# Control.net
KiCad netlist of a schematic drawn in EAGLE
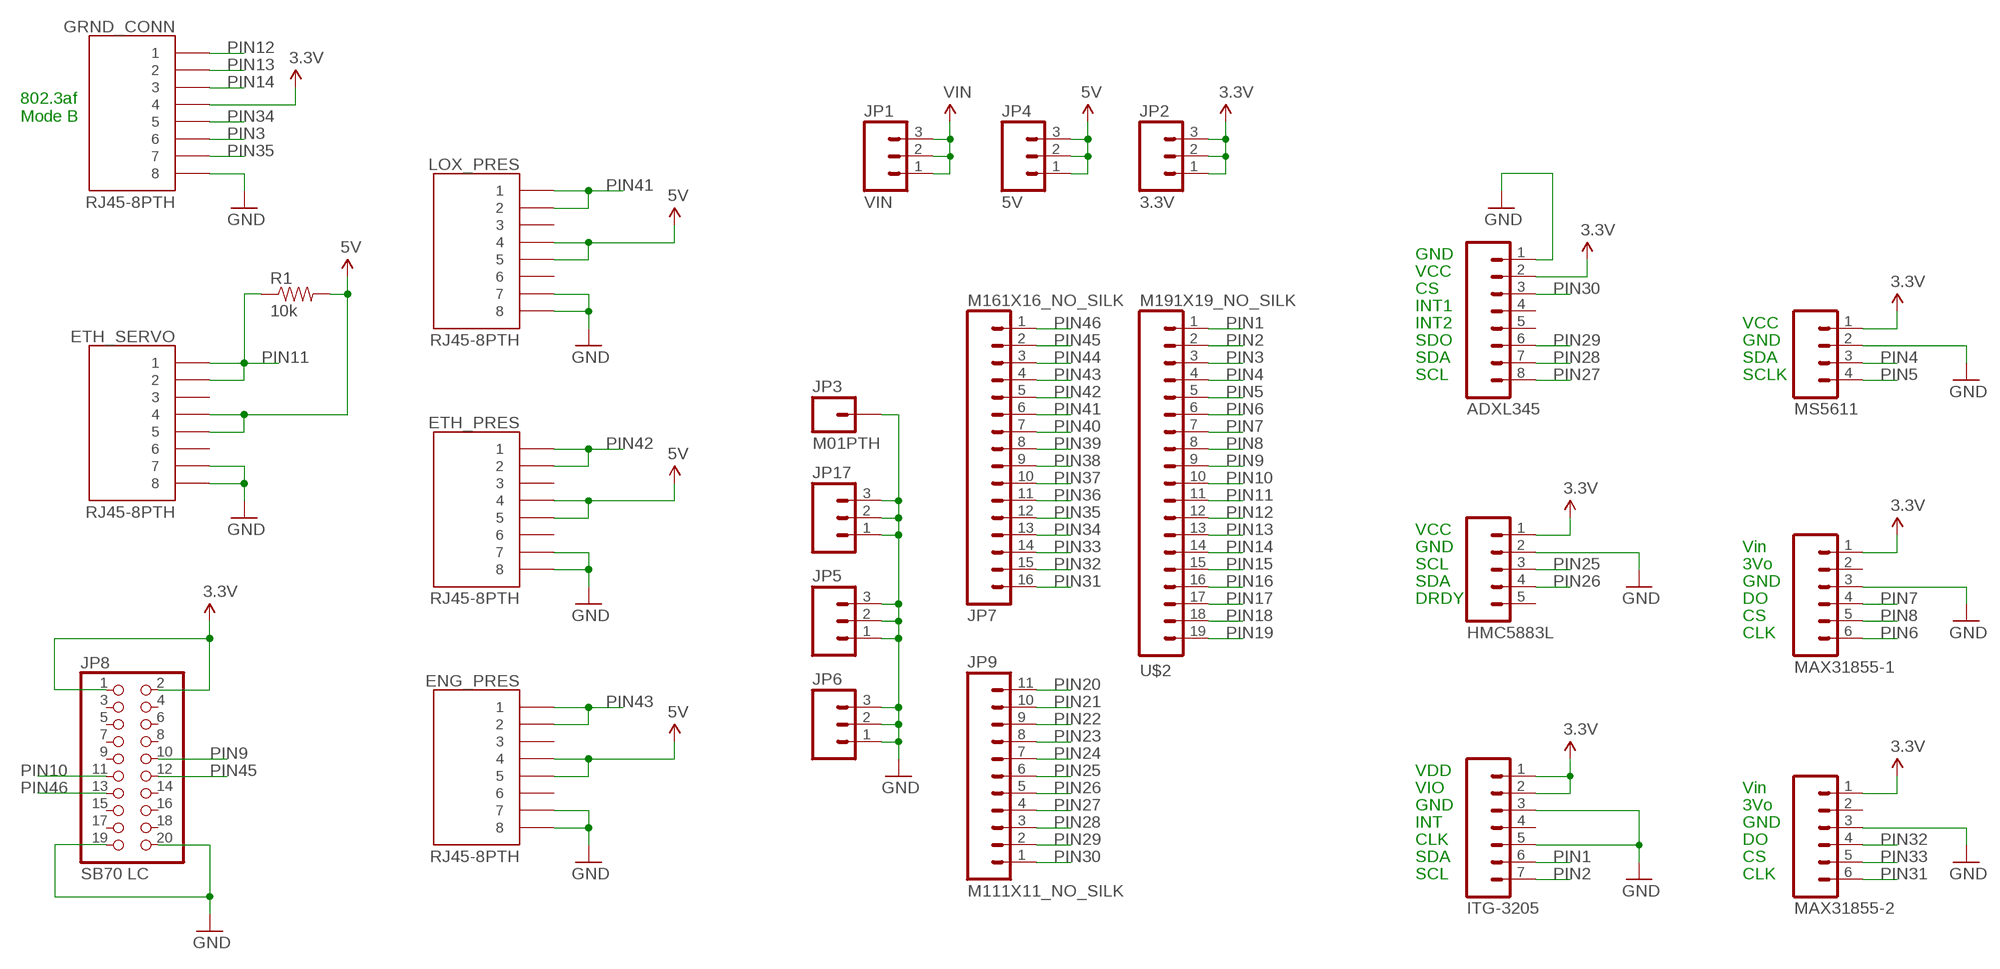
[diagram p0: schematic, sheet 1]

(export (version "E")
  (design (tool "Eeschema 10.0.6"))
  (components
    (comp (ref "ADXL345")
      (value "M081X08")
      (footprint "eagle-import:1X08")
      (libsource (lib "eagle-import") (part "M081X08"))
    )
    (comp (ref "ENG_PRES")
      (value "RJ45-8PTH")
      (footprint "eagle-import:RJ45-8")
      (libsource (lib "eagle-import") (part "RJ45-8PTH"))
    )
    (comp (ref "ETH_PRES")
      (value "RJ45-8PTH")
      (footprint "eagle-import:RJ45-8")
      (libsource (lib "eagle-import") (part "RJ45-8PTH"))
    )
    (comp (ref "ETH_SERVO")
      (value "RJ45-8PTH")
      (footprint "eagle-import:RJ45-8")
      (libsource (lib "eagle-import") (part "RJ45-8PTH"))
    )
    (comp (ref "GRND_CONN")
      (value "RJ45-8PTH")
      (footprint "eagle-import:RJ45-8")
      (libsource (lib "eagle-import") (part "RJ45-8PTH"))
    )
    (comp (ref "HMC5883L")
      (value "M05PTH")
      (footprint "eagle-import:1X05")
      (libsource (lib "eagle-import") (part "M05PTH"))
    )
    (comp (ref "ITG-3205")
      (value "M07")
      (footprint "eagle-import:1X07")
      (libsource (lib "eagle-import") (part "M07"))
    )
    (comp (ref "JP1")
      (value "VIN")
      (footprint "eagle-import:1X03")
      (libsource (lib "eagle-import") (part "M03PTH"))
    )
    (comp (ref "JP2")
      (value "3.3V")
      (footprint "eagle-import:1X03")
      (libsource (lib "eagle-import") (part "M03PTH"))
    )
    (comp (ref "JP3")
      (value "M01PTH")
      (footprint "eagle-import:1X01")
      (libsource (lib "eagle-import") (part "M01PTH"))
    )
    (comp (ref "JP4")
      (value "5V")
      (footprint "eagle-import:1X03")
      (libsource (lib "eagle-import") (part "M03PTH"))
    )
    (comp (ref "JP5")
      (value "M03PTH")
      (footprint "eagle-import:1X03")
      (libsource (lib "eagle-import") (part "M03PTH"))
    )
    (comp (ref "JP6")
      (value "M03PTH")
      (footprint "eagle-import:1X03")
      (libsource (lib "eagle-import") (part "M03PTH"))
    )
    (comp (ref "JP7")
      (value "M161X16_NO_SILK")
      (footprint "eagle-import:1X16_NO_SILK")
      (libsource (lib "eagle-import") (part "M161X16_NO_SILK"))
    )
    (comp (ref "JP8")
      (value "SB70 LC")
      (footprint "eagle-import:2X10")
      (libsource (lib "eagle-import") (part "PINHD-2X10"))
    )
    (comp (ref "JP9")
      (value "M111X11_NO_SILK")
      (footprint "eagle-import:1X11_NO_SILK")
      (libsource (lib "eagle-import") (part "M111X11_NO_SILK"))
    )
    (comp (ref "JP17")
      (value "M03PTH")
      (footprint "eagle-import:1X03")
      (libsource (lib "eagle-import") (part "M03PTH"))
    )
    (comp (ref "LOX_PRES")
      (value "RJ45-8PTH")
      (footprint "eagle-import:RJ45-8")
      (libsource (lib "eagle-import") (part "RJ45-8PTH"))
    )
    (comp (ref "MAX31855-1")
      (value "M06SIP")
      (footprint "eagle-import:1X06")
      (libsource (lib "eagle-import") (part "M06SIP"))
    )
    (comp (ref "MAX31855-2")
      (value "M06SIP")
      (footprint "eagle-import:1X06")
      (libsource (lib "eagle-import") (part "M06SIP"))
    )
    (comp (ref "MS5611")
      (value "M041X04_NO_SILK")
      (footprint "eagle-import:1X04_NO_SILK")
      (libsource (lib "eagle-import") (part "M041X04_NO_SILK"))
    )
    (comp (ref "R1")
      (value "10k")
      (footprint "eagle-import:AXIAL-0.5")
      (libsource (lib "eagle-import") (part "RESISTORPTH-1/2W"))
    )
    (comp (ref "U$2")
      (value "M191X19_NO_SILK")
      (footprint "eagle-import:1X19_NO_SILK")
      (libsource (lib "eagle-import") (part "M191X19_NO_SILK"))
    )
  )
  (nets
    (net (code "1") (name "/PIN1") (class "Default")
      (node (ref "ITG-3205") (pin "6") (pinfunction "6_6") (pintype "passive"))
      (node (ref "U$2") (pin "1") (pinfunction "1_1") (pintype "passive"))
    )
    (net (code "2") (name "/PIN2") (class "Default")
      (node (ref "ITG-3205") (pin "7") (pinfunction "7_7") (pintype "passive"))
      (node (ref "U$2") (pin "2") (pinfunction "2_2") (pintype "passive"))
    )
    (net (code "3") (name "/PIN3") (class "Default")
      (node (ref "GRND_CONN") (pin "6") (pinfunction "6_6") (pintype "bidirectional"))
      (node (ref "U$2") (pin "3") (pinfunction "3_3") (pintype "passive"))
    )
    (net (code "4") (name "/PIN4") (class "Default")
      (node (ref "MS5611") (pin "3") (pinfunction "3_3") (pintype "passive"))
      (node (ref "U$2") (pin "4") (pinfunction "4_4") (pintype "passive"))
    )
    (net (code "5") (name "/PIN5") (class "Default")
      (node (ref "MS5611") (pin "4") (pinfunction "4_4") (pintype "passive"))
      (node (ref "U$2") (pin "5") (pinfunction "5_5") (pintype "passive"))
    )
    (net (code "6") (name "/PIN6") (class "Default")
      (node (ref "MAX31855-1") (pin "6") (pinfunction "6_6") (pintype "passive"))
      (node (ref "U$2") (pin "6") (pinfunction "6_6") (pintype "passive"))
    )
    (net (code "7") (name "/PIN7") (class "Default")
      (node (ref "MAX31855-1") (pin "4") (pinfunction "4_4") (pintype "passive"))
      (node (ref "U$2") (pin "7") (pinfunction "7_7") (pintype "passive"))
    )
    (net (code "8") (name "/PIN8") (class "Default")
      (node (ref "MAX31855-1") (pin "5") (pinfunction "5_5") (pintype "passive"))
      (node (ref "U$2") (pin "8") (pinfunction "8_8") (pintype "passive"))
    )
    (net (code "9") (name "/PIN9") (class "Default")
      (node (ref "JP8") (pin "10") (pinfunction "10_10") (pintype "passive"))
      (node (ref "U$2") (pin "9") (pinfunction "9_9") (pintype "passive"))
    )
    (net (code "10") (name "/PIN10") (class "Default")
      (node (ref "JP8") (pin "11") (pinfunction "11_11") (pintype "passive"))
      (node (ref "U$2") (pin "10") (pinfunction "10_10") (pintype "passive"))
    )
    (net (code "11") (name "/PIN11") (class "Default")
      (node (ref "ETH_SERVO") (pin "1") (pinfunction "1_1") (pintype "bidirectional"))
      (node (ref "ETH_SERVO") (pin "2") (pinfunction "2_2") (pintype "bidirectional"))
      (node (ref "R1") (pin "P$1") (pinfunction "1_P$1") (pintype "passive"))
      (node (ref "U$2") (pin "11") (pinfunction "11_11") (pintype "passive"))
    )
    (net (code "12") (name "/PIN12") (class "Default")
      (node (ref "GRND_CONN") (pin "1") (pinfunction "1_1") (pintype "bidirectional"))
      (node (ref "U$2") (pin "12") (pinfunction "12_12") (pintype "passive"))
    )
    (net (code "13") (name "/PIN13") (class "Default")
      (node (ref "GRND_CONN") (pin "2") (pinfunction "2_2") (pintype "bidirectional"))
      (node (ref "U$2") (pin "13") (pinfunction "13_13") (pintype "passive"))
    )
    (net (code "14") (name "/PIN14") (class "Default")
      (node (ref "GRND_CONN") (pin "3") (pinfunction "3_3") (pintype "bidirectional"))
      (node (ref "U$2") (pin "14") (pinfunction "14_14") (pintype "passive"))
    )
    (net (code "15") (name "/PIN15") (class "Default")
      (node (ref "U$2") (pin "15") (pinfunction "15_15") (pintype "passive"))
    )
    (net (code "16") (name "/PIN16") (class "Default")
      (node (ref "U$2") (pin "16") (pinfunction "16_16") (pintype "passive"))
    )
    (net (code "17") (name "/PIN17") (class "Default")
      (node (ref "U$2") (pin "17") (pinfunction "17_17") (pintype "passive"))
    )
    (net (code "18") (name "/PIN18") (class "Default")
      (node (ref "U$2") (pin "18") (pinfunction "18_18") (pintype "passive"))
    )
    (net (code "19") (name "/PIN19") (class "Default")
      (node (ref "U$2") (pin "19") (pinfunction "19_19") (pintype "passive"))
    )
    (net (code "20") (name "/PIN20") (class "Default")
      (node (ref "JP9") (pin "11") (pinfunction "11_11") (pintype "passive"))
    )
    (net (code "21") (name "/PIN21") (class "Default")
      (node (ref "JP9") (pin "10") (pinfunction "10_10") (pintype "passive"))
    )
    (net (code "22") (name "/PIN22") (class "Default")
      (node (ref "JP9") (pin "9") (pinfunction "9_9") (pintype "passive"))
    )
    (net (code "23") (name "/PIN23") (class "Default")
      (node (ref "JP9") (pin "8") (pinfunction "8_8") (pintype "passive"))
    )
    (net (code "24") (name "/PIN24") (class "Default")
      (node (ref "JP9") (pin "7") (pinfunction "7_7") (pintype "passive"))
    )
    (net (code "25") (name "/PIN25") (class "Default")
      (node (ref "HMC5883L") (pin "3") (pinfunction "3_3") (pintype "passive"))
      (node (ref "JP9") (pin "6") (pinfunction "6_6") (pintype "passive"))
    )
    (net (code "26") (name "/PIN26") (class "Default")
      (node (ref "HMC5883L") (pin "4") (pinfunction "4_4") (pintype "passive"))
      (node (ref "JP9") (pin "5") (pinfunction "5_5") (pintype "passive"))
    )
    (net (code "27") (name "/PIN27") (class "Default")
      (node (ref "ADXL345") (pin "8") (pinfunction "8_8") (pintype "passive"))
      (node (ref "JP9") (pin "4") (pinfunction "4_4") (pintype "passive"))
    )
    (net (code "28") (name "/PIN28") (class "Default")
      (node (ref "ADXL345") (pin "7") (pinfunction "7_7") (pintype "passive"))
      (node (ref "JP9") (pin "3") (pinfunction "3_3") (pintype "passive"))
    )
    (net (code "29") (name "/PIN29") (class "Default")
      (node (ref "ADXL345") (pin "6") (pinfunction "6_6") (pintype "passive"))
      (node (ref "JP9") (pin "2") (pinfunction "2_2") (pintype "passive"))
    )
    (net (code "30") (name "/PIN30") (class "Default")
      (node (ref "ADXL345") (pin "3") (pinfunction "3_3") (pintype "passive"))
      (node (ref "JP9") (pin "1") (pinfunction "1_1") (pintype "passive"))
    )
    (net (code "31") (name "/PIN31") (class "Default")
      (node (ref "JP7") (pin "16") (pinfunction "16_16") (pintype "passive"))
      (node (ref "MAX31855-2") (pin "6") (pinfunction "6_6") (pintype "passive"))
    )
    (net (code "32") (name "/PIN32") (class "Default")
      (node (ref "JP7") (pin "15") (pinfunction "15_15") (pintype "passive"))
      (node (ref "MAX31855-2") (pin "4") (pinfunction "4_4") (pintype "passive"))
    )
    (net (code "33") (name "/PIN33") (class "Default")
      (node (ref "JP7") (pin "14") (pinfunction "14_14") (pintype "passive"))
      (node (ref "MAX31855-2") (pin "5") (pinfunction "5_5") (pintype "passive"))
    )
    (net (code "34") (name "/PIN34") (class "Default")
      (node (ref "GRND_CONN") (pin "5") (pinfunction "5_5") (pintype "bidirectional"))
      (node (ref "JP7") (pin "13") (pinfunction "13_13") (pintype "passive"))
    )
    (net (code "35") (name "/PIN35") (class "Default")
      (node (ref "GRND_CONN") (pin "7") (pinfunction "7_7") (pintype "bidirectional"))
      (node (ref "JP7") (pin "12") (pinfunction "12_12") (pintype "passive"))
    )
    (net (code "36") (name "/PIN36") (class "Default")
      (node (ref "JP7") (pin "11") (pinfunction "11_11") (pintype "passive"))
    )
    (net (code "37") (name "/PIN37") (class "Default")
      (node (ref "JP7") (pin "10") (pinfunction "10_10") (pintype "passive"))
    )
    (net (code "38") (name "/PIN38") (class "Default")
      (node (ref "JP7") (pin "9") (pinfunction "9_9") (pintype "passive"))
    )
    (net (code "39") (name "/PIN39") (class "Default")
      (node (ref "JP7") (pin "8") (pinfunction "8_8") (pintype "passive"))
    )
    (net (code "40") (name "/PIN40") (class "Default")
      (node (ref "JP7") (pin "7") (pinfunction "7_7") (pintype "passive"))
    )
    (net (code "41") (name "/PIN41") (class "Default")
      (node (ref "JP7") (pin "6") (pinfunction "6_6") (pintype "passive"))
      (node (ref "LOX_PRES") (pin "1") (pinfunction "1_1") (pintype "bidirectional"))
      (node (ref "LOX_PRES") (pin "2") (pinfunction "2_2") (pintype "bidirectional"))
    )
    (net (code "42") (name "/PIN42") (class "Default")
      (node (ref "ETH_PRES") (pin "1") (pinfunction "1_1") (pintype "bidirectional"))
      (node (ref "ETH_PRES") (pin "2") (pinfunction "2_2") (pintype "bidirectional"))
      (node (ref "JP7") (pin "5") (pinfunction "5_5") (pintype "passive"))
    )
    (net (code "43") (name "/PIN43") (class "Default")
      (node (ref "ENG_PRES") (pin "1") (pinfunction "1_1") (pintype "bidirectional"))
      (node (ref "ENG_PRES") (pin "2") (pinfunction "2_2") (pintype "bidirectional"))
      (node (ref "JP7") (pin "4") (pinfunction "4_4") (pintype "passive"))
    )
    (net (code "44") (name "/PIN44") (class "Default")
      (node (ref "JP7") (pin "3") (pinfunction "3_3") (pintype "passive"))
    )
    (net (code "45") (name "/PIN45") (class "Default")
      (node (ref "JP7") (pin "2") (pinfunction "2_2") (pintype "passive"))
      (node (ref "JP8") (pin "12") (pinfunction "12_12") (pintype "passive"))
    )
    (net (code "46") (name "/PIN46") (class "Default")
      (node (ref "JP7") (pin "1") (pinfunction "1_1") (pintype "passive"))
      (node (ref "JP8") (pin "13") (pinfunction "13_13") (pintype "passive"))
    )
    (net (code "47") (name "3.3V") (class "Default")
      (node (ref "ADXL345") (pin "2") (pinfunction "2_2") (pintype "passive"))
      (node (ref "GRND_CONN") (pin "4") (pinfunction "4_4") (pintype "bidirectional"))
      (node (ref "HMC5883L") (pin "1") (pinfunction "1_1") (pintype "passive"))
      (node (ref "ITG-3205") (pin "1") (pinfunction "1_1") (pintype "passive"))
      (node (ref "ITG-3205") (pin "2") (pinfunction "2_2") (pintype "passive"))
      (node (ref "JP2") (pin "1") (pinfunction "1_1") (pintype "passive"))
      (node (ref "JP2") (pin "2") (pinfunction "2_2") (pintype "passive"))
      (node (ref "JP2") (pin "3") (pinfunction "3_3") (pintype "passive"))
      (node (ref "JP8") (pin "1") (pinfunction "1_1") (pintype "passive"))
      (node (ref "JP8") (pin "2") (pinfunction "2_2") (pintype "passive"))
      (node (ref "MAX31855-1") (pin "1") (pinfunction "1_1") (pintype "passive"))
      (node (ref "MAX31855-2") (pin "1") (pinfunction "1_1") (pintype "passive"))
      (node (ref "MS5611") (pin "1") (pinfunction "1_1") (pintype "passive"))
    )
    (net (code "48") (name "5V") (class "Default")
      (node (ref "ENG_PRES") (pin "4") (pinfunction "4_4") (pintype "bidirectional"))
      (node (ref "ENG_PRES") (pin "5") (pinfunction "5_5") (pintype "bidirectional"))
      (node (ref "ETH_PRES") (pin "4") (pinfunction "4_4") (pintype "bidirectional"))
      (node (ref "ETH_PRES") (pin "5") (pinfunction "5_5") (pintype "bidirectional"))
      (node (ref "ETH_SERVO") (pin "4") (pinfunction "4_4") (pintype "bidirectional"))
      (node (ref "ETH_SERVO") (pin "5") (pinfunction "5_5") (pintype "bidirectional"))
      (node (ref "JP4") (pin "1") (pinfunction "1_1") (pintype "passive"))
      (node (ref "JP4") (pin "2") (pinfunction "2_2") (pintype "passive"))
      (node (ref "JP4") (pin "3") (pinfunction "3_3") (pintype "passive"))
      (node (ref "LOX_PRES") (pin "4") (pinfunction "4_4") (pintype "bidirectional"))
      (node (ref "LOX_PRES") (pin "5") (pinfunction "5_5") (pintype "bidirectional"))
      (node (ref "R1") (pin "P$2") (pinfunction "2_P$2") (pintype "passive"))
    )
    (net (code "49") (name "GND") (class "Default")
      (node (ref "ADXL345") (pin "1") (pinfunction "1_1") (pintype "passive"))
      (node (ref "ENG_PRES") (pin "7") (pinfunction "7_7") (pintype "bidirectional"))
      (node (ref "ENG_PRES") (pin "8") (pinfunction "8_8") (pintype "bidirectional"))
      (node (ref "ETH_PRES") (pin "7") (pinfunction "7_7") (pintype "bidirectional"))
      (node (ref "ETH_PRES") (pin "8") (pinfunction "8_8") (pintype "bidirectional"))
      (node (ref "ETH_SERVO") (pin "7") (pinfunction "7_7") (pintype "bidirectional"))
      (node (ref "ETH_SERVO") (pin "8") (pinfunction "8_8") (pintype "bidirectional"))
      (node (ref "GRND_CONN") (pin "8") (pinfunction "8_8") (pintype "bidirectional"))
      (node (ref "HMC5883L") (pin "2") (pinfunction "2_2") (pintype "passive"))
      (node (ref "ITG-3205") (pin "3") (pinfunction "3_3") (pintype "passive"))
      (node (ref "ITG-3205") (pin "5") (pinfunction "5_5") (pintype "passive"))
      (node (ref "JP17") (pin "1") (pinfunction "1_1") (pintype "passive"))
      (node (ref "JP17") (pin "2") (pinfunction "2_2") (pintype "passive"))
      (node (ref "JP17") (pin "3") (pinfunction "3_3") (pintype "passive"))
      (node (ref "JP3") (pin "1") (pinfunction "1_1") (pintype "passive"))
      (node (ref "JP5") (pin "1") (pinfunction "1_1") (pintype "passive"))
      (node (ref "JP5") (pin "2") (pinfunction "2_2") (pintype "passive"))
      (node (ref "JP5") (pin "3") (pinfunction "3_3") (pintype "passive"))
      (node (ref "JP6") (pin "1") (pinfunction "1_1") (pintype "passive"))
      (node (ref "JP6") (pin "2") (pinfunction "2_2") (pintype "passive"))
      (node (ref "JP6") (pin "3") (pinfunction "3_3") (pintype "passive"))
      (node (ref "JP8") (pin "19") (pinfunction "19_19") (pintype "passive"))
      (node (ref "JP8") (pin "20") (pinfunction "20_20") (pintype "passive"))
      (node (ref "LOX_PRES") (pin "7") (pinfunction "7_7") (pintype "bidirectional"))
      (node (ref "LOX_PRES") (pin "8") (pinfunction "8_8") (pintype "bidirectional"))
      (node (ref "MAX31855-1") (pin "3") (pinfunction "3_3") (pintype "passive"))
      (node (ref "MAX31855-2") (pin "3") (pinfunction "3_3") (pintype "passive"))
      (node (ref "MS5611") (pin "2") (pinfunction "2_2") (pintype "passive"))
    )
    (net (code "50") (name "VIN") (class "Default")
      (node (ref "JP1") (pin "1") (pinfunction "1_1") (pintype "passive"))
      (node (ref "JP1") (pin "2") (pinfunction "2_2") (pintype "passive"))
      (node (ref "JP1") (pin "3") (pinfunction "3_3") (pintype "passive"))
    )
    (net (code "51") (name "unconnected-(ADXL345-Pad4)") (class "Default")
      (node (ref "ADXL345") (pin "4") (pinfunction "4_4") (pintype "passive"))
    )
    (net (code "52") (name "unconnected-(ADXL345-Pad5)") (class "Default")
      (node (ref "ADXL345") (pin "5") (pinfunction "5_5") (pintype "passive"))
    )
    (net (code "53") (name "unconnected-(ENG_PRES-Pad3)") (class "Default")
      (node (ref "ENG_PRES") (pin "3") (pinfunction "3_3") (pintype "bidirectional"))
    )
    (net (code "54") (name "unconnected-(ENG_PRES-Pad6)") (class "Default")
      (node (ref "ENG_PRES") (pin "6") (pinfunction "6_6") (pintype "bidirectional"))
    )
    (net (code "55") (name "unconnected-(ETH_PRES-Pad3)") (class "Default")
      (node (ref "ETH_PRES") (pin "3") (pinfunction "3_3") (pintype "bidirectional"))
    )
    (net (code "56") (name "unconnected-(ETH_PRES-Pad6)") (class "Default")
      (node (ref "ETH_PRES") (pin "6") (pinfunction "6_6") (pintype "bidirectional"))
    )
    (net (code "57") (name "unconnected-(ETH_SERVO-Pad3)") (class "Default")
      (node (ref "ETH_SERVO") (pin "3") (pinfunction "3_3") (pintype "bidirectional"))
    )
    (net (code "58") (name "unconnected-(ETH_SERVO-Pad6)") (class "Default")
      (node (ref "ETH_SERVO") (pin "6") (pinfunction "6_6") (pintype "bidirectional"))
    )
    (net (code "59") (name "unconnected-(HMC5883L-Pad5)") (class "Default")
      (node (ref "HMC5883L") (pin "5") (pinfunction "5_5") (pintype "passive"))
    )
    (net (code "60") (name "unconnected-(ITG-3205-Pad4)") (class "Default")
      (node (ref "ITG-3205") (pin "4") (pinfunction "4_4") (pintype "passive"))
    )
    (net (code "61") (name "unconnected-(JP8-Pad3)") (class "Default")
      (node (ref "JP8") (pin "3") (pinfunction "3_3") (pintype "passive"))
    )
    (net (code "62") (name "unconnected-(JP8-Pad4)") (class "Default")
      (node (ref "JP8") (pin "4") (pinfunction "4_4") (pintype "passive"))
    )
    (net (code "63") (name "unconnected-(JP8-Pad5)") (class "Default")
      (node (ref "JP8") (pin "5") (pinfunction "5_5") (pintype "passive"))
    )
    (net (code "64") (name "unconnected-(JP8-Pad6)") (class "Default")
      (node (ref "JP8") (pin "6") (pinfunction "6_6") (pintype "passive"))
    )
    (net (code "65") (name "unconnected-(JP8-Pad7)") (class "Default")
      (node (ref "JP8") (pin "7") (pinfunction "7_7") (pintype "passive"))
    )
    (net (code "66") (name "unconnected-(JP8-Pad8)") (class "Default")
      (node (ref "JP8") (pin "8") (pinfunction "8_8") (pintype "passive"))
    )
    (net (code "67") (name "unconnected-(JP8-Pad9)") (class "Default")
      (node (ref "JP8") (pin "9") (pinfunction "9_9") (pintype "passive"))
    )
    (net (code "68") (name "unconnected-(JP8-Pad14)") (class "Default")
      (node (ref "JP8") (pin "14") (pinfunction "14_14") (pintype "passive"))
    )
    (net (code "69") (name "unconnected-(JP8-Pad15)") (class "Default")
      (node (ref "JP8") (pin "15") (pinfunction "15_15") (pintype "passive"))
    )
    (net (code "70") (name "unconnected-(JP8-Pad16)") (class "Default")
      (node (ref "JP8") (pin "16") (pinfunction "16_16") (pintype "passive"))
    )
    (net (code "71") (name "unconnected-(JP8-Pad17)") (class "Default")
      (node (ref "JP8") (pin "17") (pinfunction "17_17") (pintype "passive"))
    )
    (net (code "72") (name "unconnected-(JP8-Pad18)") (class "Default")
      (node (ref "JP8") (pin "18") (pinfunction "18_18") (pintype "passive"))
    )
    (net (code "73") (name "unconnected-(LOX_PRES-Pad3)") (class "Default")
      (node (ref "LOX_PRES") (pin "3") (pinfunction "3_3") (pintype "bidirectional"))
    )
    (net (code "74") (name "unconnected-(LOX_PRES-Pad6)") (class "Default")
      (node (ref "LOX_PRES") (pin "6") (pinfunction "6_6") (pintype "bidirectional"))
    )
    (net (code "75") (name "unconnected-(MAX31855-1-Pad2)") (class "Default")
      (node (ref "MAX31855-1") (pin "2") (pinfunction "2_2") (pintype "passive"))
    )
    (net (code "76") (name "unconnected-(MAX31855-2-Pad2)") (class "Default")
      (node (ref "MAX31855-2") (pin "2") (pinfunction "2_2") (pintype "passive"))
    )
  )
)
